# 6P1.net
KiCad netlist of a schematic drawn in Altium Designer
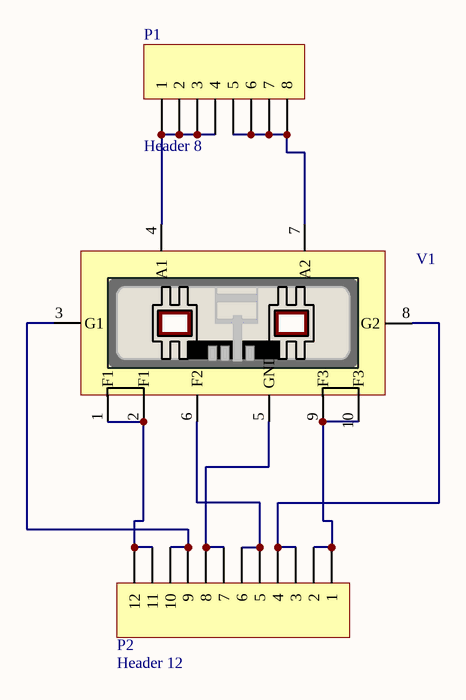
[diagram p0: 6P1.SchDoc]

(export (version "E")
  (design (tool "Eeschema 10.0.6"))
  (components
    (comp (ref "P1")
      (value "Header 8")
      (footprint "HDR1X8")
      (description "Header, 8-Pin")
      (fields (field (name "PUBLISHER") "Altium Limited"))
      (libsource (lib "Miscellaneous Connectors") (part "Header 8"))
    )
    (comp (ref "P2")
      (value "Header 12")
      (footprint "HDR1X12")
      (description "Header, 12-Pin")
      (fields (field (name "PUBLISHER") "Altium Limited"))
      (libsource (lib "Miscellaneous Connectors") (part "Header 12"))
    )
    (comp (ref "V1")
      (value "Nutube 6P1")
      (footprint "Nutube 6P1")
      (libsource (lib "Audio Board") (part "Nutube 6P1"))
    )
  )
  (nets
    (net (code "1") (name "Net-(P2-Pad1)") (class "Default")
      (node (ref "P2") (pin "1") (pinfunction "1_1") (pintype "passive"))
      (node (ref "P2") (pin "2") (pinfunction "2_2") (pintype "passive"))
      (node (ref "V1") (pin "10") (pinfunction "F3_10") (pintype "passive"))
      (node (ref "V1") (pin "9") (pinfunction "F3_9") (pintype "passive"))
    )
    (net (code "2") (name "Net-(P2-Pad11)") (class "Default")
      (node (ref "P2") (pin "11") (pinfunction "11_11") (pintype "passive"))
      (node (ref "P2") (pin "12") (pinfunction "12_12") (pintype "passive"))
      (node (ref "V1") (pin "1") (pinfunction "F1_1") (pintype "passive"))
      (node (ref "V1") (pin "2") (pinfunction "F1_2") (pintype "passive"))
    )
    (net (code "3") (name "Net-(V1-A1)") (class "Default")
      (node (ref "P1") (pin "1") (pinfunction "1_1") (pintype "passive"))
      (node (ref "P1") (pin "2") (pinfunction "2_2") (pintype "passive"))
      (node (ref "P1") (pin "3") (pinfunction "3_3") (pintype "passive"))
      (node (ref "P1") (pin "4") (pinfunction "4_4") (pintype "passive"))
      (node (ref "V1") (pin "4") (pinfunction "A1_4") (pintype "passive"))
    )
    (net (code "4") (name "Net-(V1-A2)") (class "Default")
      (node (ref "P1") (pin "5") (pinfunction "5_5") (pintype "passive"))
      (node (ref "P1") (pin "6") (pinfunction "6_6") (pintype "passive"))
      (node (ref "P1") (pin "7") (pinfunction "7_7") (pintype "passive"))
      (node (ref "P1") (pin "8") (pinfunction "8_8") (pintype "passive"))
      (node (ref "V1") (pin "7") (pinfunction "A2_7") (pintype "passive"))
    )
    (net (code "5") (name "Net-(V1-F2)") (class "Default")
      (node (ref "P2") (pin "5") (pinfunction "5_5") (pintype "passive"))
      (node (ref "P2") (pin "6") (pinfunction "6_6") (pintype "passive"))
      (node (ref "V1") (pin "6") (pinfunction "F2_6") (pintype "passive"))
    )
    (net (code "6") (name "Net-(V1-G1)") (class "Default")
      (node (ref "P2") (pin "10") (pinfunction "10_10") (pintype "passive"))
      (node (ref "P2") (pin "9") (pinfunction "9_9") (pintype "passive"))
      (node (ref "V1") (pin "3") (pinfunction "G1_3") (pintype "passive"))
    )
    (net (code "7") (name "Net-(V1-G2)") (class "Default")
      (node (ref "P2") (pin "3") (pinfunction "3_3") (pintype "passive"))
      (node (ref "P2") (pin "4") (pinfunction "4_4") (pintype "passive"))
      (node (ref "V1") (pin "8") (pinfunction "G2_8") (pintype "passive"))
    )
    (net (code "8") (name "Net-(V1-GND)") (class "Default")
      (node (ref "P2") (pin "7") (pinfunction "7_7") (pintype "passive"))
      (node (ref "P2") (pin "8") (pinfunction "8_8") (pintype "passive"))
      (node (ref "V1") (pin "5") (pinfunction "GND_5") (pintype "passive"))
    )
  )
)
